# Temperature_Sensor.net
KiCad netlist of a schematic drawn in Altium Designer
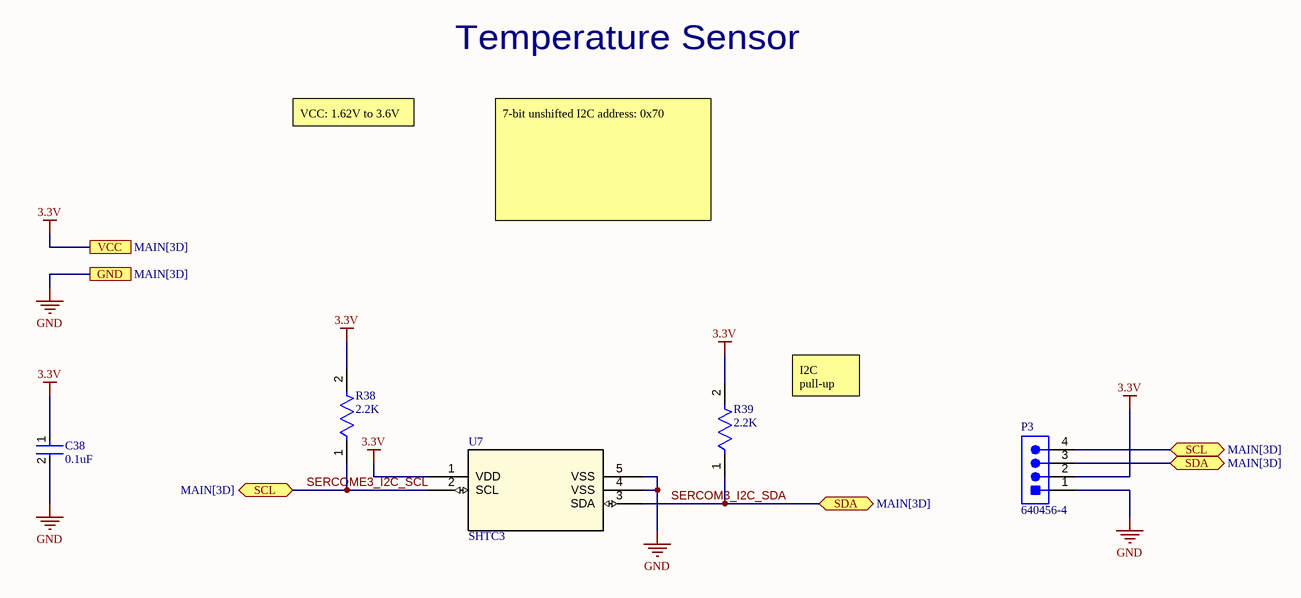
[diagram p0: Temperature_Sensor.SchDoc]

(export (version "E")
  (design (tool "Eeschema 10.0.6"))
  (components
    (comp (ref "C38")
      (value "0.1uF")
      (footprint "FP-C0402-BB-MFG")
      (description "CAP CER 0402 0.1UF 16V X7R 20% A")
      (fields
        (field (name "OCTOPART") "https://octopart.com/c0402c104m4racauto-kemet-75357841")
        (field (name "TOLERANCE") "0.2")
      )
      (libsource (lib "Altium Content Vault") (part "b4654b650e69147ec39a6b967a45e02"))
    )
    (comp (ref "P3")
      (value "640456-4")
      (footprint "TECO-640456-4")
      (description "Male Header, Pitch 2.54 mm, 1 x 4 Position, Height 10.03 mm, Tail Length 3.56 mm, RoHS, Bulk")
      (fields (field (name "MANUFACTURER") "TE Connectivity"))
      (libsource (lib "Altium Content Vault") (part "CN-1P-M-R4"))
    )
    (comp (ref "R38")
      (value "2.2K")
      (footprint "FP-SR0402-MFG")
      (description "RES 2.2K OHM 1% 1/5W 0402")
      (fields (field (name "MANUFACTURER PART NUMBER") "SR0402FR-7T2K2L") (field (name "TOLERANCE") "0.01"))
      (libsource (lib "Altium Content Vault") (part "1029c3af85768c4190bb7ad29bc67b5"))
    )
    (comp (ref "R39")
      (value "2.2K")
      (footprint "FP-SR0402-MFG")
      (description "RES 2.2K OHM 1% 1/5W 0402")
      (fields (field (name "MANUFACTURER PART NUMBER") "SR0402FR-7T2K2L") (field (name "TOLERANCE") "0.01"))
      (libsource (lib "Altium Content Vault") (part "1029c3af85768c4190bb7ad29bc67b5"))
    )
    (comp (ref "U7")
      (value "SHTC3")
      (footprint "SHTC3_SEN")
      (description "No Description Available")
      (fields (field (name "COPYRIGHT") "Copyright (C) 2022 Ultra Librarian. All rights reserved."))
      (libsource (lib "Schematics") (part "SHTC3"))
    )
  )
  (nets
    (net (code "1") (name "/SERCOM3_I2C_SDA") (class "Default")
      (node (ref "P3") (pin "3") (pinfunction "3_3") (pintype "passive"))
      (node (ref "R39") (pin "1") (pinfunction "1_1") (pintype "passive"))
      (node (ref "U7") (pin "3") (pinfunction "SDA_3") (pintype "bidirectional"))
    )
    (net (code "2") (name "/SERCOME3_I2C_SCL") (class "Default")
      (node (ref "P3") (pin "4") (pinfunction "4_4") (pintype "passive"))
      (node (ref "R38") (pin "1") (pinfunction "1_1") (pintype "passive"))
      (node (ref "U7") (pin "2") (pinfunction "SCL_2") (pintype "bidirectional"))
    )
    (net (code "3") (name "3.3V") (class "Default")
      (node (ref "C38") (pin "1") (pinfunction "1_1") (pintype "passive"))
      (node (ref "P3") (pin "2") (pinfunction "2_2") (pintype "passive"))
      (node (ref "R38") (pin "2") (pinfunction "2_2") (pintype "passive"))
      (node (ref "R39") (pin "2") (pinfunction "2_2") (pintype "passive"))
      (node (ref "U7") (pin "1") (pinfunction "VDD_1") (pintype "power_in"))
    )
    (net (code "4") (name "GND") (class "Default")
      (node (ref "C38") (pin "2") (pinfunction "2_2") (pintype "passive"))
      (node (ref "P3") (pin "1") (pinfunction "1_1") (pintype "passive"))
      (node (ref "U7") (pin "4") (pinfunction "VSS_4") (pintype "passive"))
      (node (ref "U7") (pin "5") (pinfunction "VSS_5") (pintype "passive"))
    )
  )
)
